# 2_MEMORY.net
KiCad netlist of a schematic drawn in Altium Designer
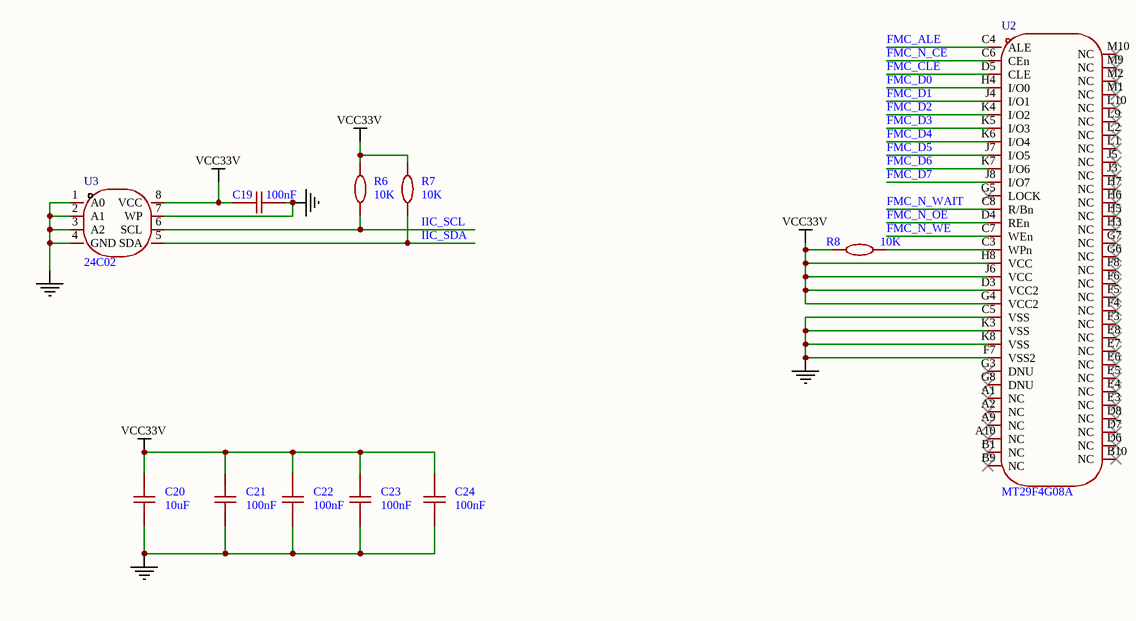
[diagram p0: 2_MEMORY.schdoc]

(export (version "E")
  (design (tool "Eeschema 10.0.6"))
  (components
    (comp (ref "C19")
      (value "100nF")
      (footprint "C0402")
      (libsource (lib "altium-import") (part "root_2_CAP_0402_"))
    )
    (comp (ref "C20")
      (value "10uF")
      (footprint "C0603")
      (libsource (lib "altium-import") (part "root_1_CAP_0603_"))
    )
    (comp (ref "C21")
      (value "100nF")
      (footprint "C0402")
      (libsource (lib "altium-import") (part "root_1_CAP_0402_"))
    )
    (comp (ref "C22")
      (value "100nF")
      (footprint "C0402")
      (libsource (lib "altium-import") (part "root_1_CAP_0402_"))
    )
    (comp (ref "C23")
      (value "100nF")
      (footprint "C0402")
      (libsource (lib "altium-import") (part "root_1_CAP_0402_"))
    )
    (comp (ref "C24")
      (value "100nF")
      (footprint "C0402")
      (libsource (lib "altium-import") (part "root_1_CAP_0402_"))
    )
    (comp (ref "R6")
      (value "10K")
      (footprint "R0402")
      (libsource (lib "altium-import") (part "root_1_Res_0402_"))
    )
    (comp (ref "R7")
      (value "10K")
      (footprint "R0402")
      (libsource (lib "altium-import") (part "root_1_Res_0402_"))
    )
    (comp (ref "R8")
      (value "10K")
      (footprint "R0402")
      (libsource (lib "altium-import") (part "root_0_Res_0402_"))
    )
    (comp (ref "U2")
      (value "MT29F4G08A")
      (footprint "VFBGA-63_L11.0-W9.0-P0.80-BL_MT29F2G08ABAEAH4-IT-E")
      (libsource (lib "altium-import") (part "root_0_MT29F4G08A_"))
    )
    (comp (ref "U3")
      (value "24C02")
      (footprint "SOP-8_L4.9-W3.9-P1.27-LS6.0-BL")
      (libsource (lib "altium-import") (part "root_0_24C02_"))
    )
  )
  (nets
    (net (code "1") (name "/FMC_ALE") (class "Default")
      (node (ref "U2") (pin "C4") (pinfunction "ALE_C4") (pintype "passive"))
    )
    (net (code "2") (name "/FMC_CLE") (class "Default")
      (node (ref "U2") (pin "D5") (pinfunction "CLE_D5") (pintype "passive"))
    )
    (net (code "3") (name "/FMC_D0") (class "Default")
      (node (ref "U2") (pin "H4") (pinfunction "I/O0_H4") (pintype "passive"))
    )
    (net (code "4") (name "/FMC_D1") (class "Default")
      (node (ref "U2") (pin "J4") (pinfunction "I/O1_J4") (pintype "passive"))
    )
    (net (code "5") (name "/FMC_D2") (class "Default")
      (node (ref "U2") (pin "K4") (pinfunction "I/O2_K4") (pintype "passive"))
    )
    (net (code "6") (name "/FMC_D3") (class "Default")
      (node (ref "U2") (pin "K5") (pinfunction "I/O3_K5") (pintype "passive"))
    )
    (net (code "7") (name "/FMC_D4") (class "Default")
      (node (ref "U2") (pin "K6") (pinfunction "I/O4_K6") (pintype "passive"))
    )
    (net (code "8") (name "/FMC_D5") (class "Default")
      (node (ref "U2") (pin "J7") (pinfunction "I/O5_J7") (pintype "passive"))
    )
    (net (code "9") (name "/FMC_D6") (class "Default")
      (node (ref "U2") (pin "K7") (pinfunction "I/O6_K7") (pintype "passive"))
    )
    (net (code "10") (name "/FMC_D7") (class "Default")
      (node (ref "U2") (pin "J8") (pinfunction "I/O7_J8") (pintype "passive"))
    )
    (net (code "11") (name "/FMC_N_CE") (class "Default")
      (node (ref "U2") (pin "C6") (pinfunction "CEn_C6") (pintype "passive"))
    )
    (net (code "12") (name "/FMC_N_OE") (class "Default")
      (node (ref "U2") (pin "D4") (pinfunction "REn_D4") (pintype "passive"))
    )
    (net (code "13") (name "/FMC_N_WAIT") (class "Default")
      (node (ref "U2") (pin "C8") (pinfunction "R/Bn_C8") (pintype "passive"))
    )
    (net (code "14") (name "/FMC_N_WE") (class "Default")
      (node (ref "U2") (pin "C7") (pinfunction "WEn_C7") (pintype "passive"))
    )
    (net (code "15") (name "/IIC_SCL") (class "Default")
      (node (ref "R6") (pin "1") (pinfunction "1_1") (pintype "passive"))
      (node (ref "U3") (pin "6") (pinfunction "SCL_6") (pintype "passive"))
    )
    (net (code "16") (name "/IIC_SDA") (class "Default")
      (node (ref "R7") (pin "1") (pinfunction "1_1") (pintype "passive"))
      (node (ref "U3") (pin "5") (pinfunction "SDA_5") (pintype "passive"))
    )
    (net (code "17") (name "DGND") (class "Default")
      (node (ref "C19") (pin "1") (pinfunction "1_1") (pintype "passive"))
      (node (ref "C20") (pin "1") (pinfunction "1_1") (pintype "passive"))
      (node (ref "C21") (pin "1") (pinfunction "1_1") (pintype "passive"))
      (node (ref "C22") (pin "1") (pinfunction "1_1") (pintype "passive"))
      (node (ref "C23") (pin "1") (pinfunction "1_1") (pintype "passive"))
      (node (ref "C24") (pin "1") (pinfunction "1_1") (pintype "passive"))
      (node (ref "U2") (pin "C5") (pinfunction "VSS_C5") (pintype "passive"))
      (node (ref "U2") (pin "F7") (pinfunction "VSS2_F7") (pintype "passive"))
      (node (ref "U2") (pin "K3") (pinfunction "VSS_K3") (pintype "passive"))
      (node (ref "U2") (pin "K8") (pinfunction "VSS_K8") (pintype "passive"))
      (node (ref "U3") (pin "1") (pinfunction "A0_1") (pintype "passive"))
      (node (ref "U3") (pin "2") (pinfunction "A1_2") (pintype "passive"))
      (node (ref "U3") (pin "3") (pinfunction "A2_3") (pintype "passive"))
      (node (ref "U3") (pin "4") (pinfunction "GND_4") (pintype "passive"))
      (node (ref "U3") (pin "7") (pinfunction "WP_7") (pintype "passive"))
    )
    (net (code "18") (name "Net-(U2-WPn)") (class "Default")
      (node (ref "R8") (pin "2") (pinfunction "2_2") (pintype "passive"))
      (node (ref "U2") (pin "C3") (pinfunction "WPn_C3") (pintype "passive"))
    )
    (net (code "19") (name "VCC33V") (class "Default")
      (node (ref "C19") (pin "2") (pinfunction "2_2") (pintype "passive"))
      (node (ref "C20") (pin "2") (pinfunction "2_2") (pintype "passive"))
      (node (ref "C21") (pin "2") (pinfunction "2_2") (pintype "passive"))
      (node (ref "C22") (pin "2") (pinfunction "2_2") (pintype "passive"))
      (node (ref "C23") (pin "2") (pinfunction "2_2") (pintype "passive"))
      (node (ref "C24") (pin "2") (pinfunction "2_2") (pintype "passive"))
      (node (ref "R6") (pin "2") (pinfunction "2_2") (pintype "passive"))
      (node (ref "R7") (pin "2") (pinfunction "2_2") (pintype "passive"))
      (node (ref "R8") (pin "1") (pinfunction "1_1") (pintype "passive"))
      (node (ref "U2") (pin "D3") (pinfunction "VCC2_D3") (pintype "passive"))
      (node (ref "U2") (pin "G4") (pinfunction "VCC2_G4") (pintype "passive"))
      (node (ref "U2") (pin "H8") (pinfunction "VCC_H8") (pintype "passive"))
      (node (ref "U2") (pin "J6") (pinfunction "VCC_J6") (pintype "passive"))
      (node (ref "U3") (pin "8") (pinfunction "VCC_8") (pintype "passive"))
    )
    (net (code "20") (name "unconnected-(U2-DNU-PadG3)") (class "Default")
      (node (ref "U2") (pin "G3") (pinfunction "DNU_G3") (pintype "passive+no_connect"))
    )
    (net (code "21") (name "unconnected-(U2-DNU-PadG8)") (class "Default")
      (node (ref "U2") (pin "G8") (pinfunction "DNU_G8") (pintype "passive+no_connect"))
    )
    (net (code "22") (name "unconnected-(U2-LOCK-PadG5)") (class "Default")
      (node (ref "U2") (pin "G5") (pinfunction "LOCK_G5") (pintype "passive+no_connect"))
    )
    (net (code "23") (name "unconnected-(U2-NC-PadA1)") (class "Default")
      (node (ref "U2") (pin "A1") (pinfunction "NC_A1") (pintype "passive+no_connect"))
    )
    (net (code "24") (name "unconnected-(U2-NC-PadA2)") (class "Default")
      (node (ref "U2") (pin "A2") (pinfunction "NC_A2") (pintype "passive+no_connect"))
    )
    (net (code "25") (name "unconnected-(U2-NC-PadA9)") (class "Default")
      (node (ref "U2") (pin "A9") (pinfunction "NC_A9") (pintype "passive+no_connect"))
    )
    (net (code "26") (name "unconnected-(U2-NC-PadA10)") (class "Default")
      (node (ref "U2") (pin "A10") (pinfunction "NC_A10") (pintype "passive+no_connect"))
    )
    (net (code "27") (name "unconnected-(U2-NC-PadB1)") (class "Default")
      (node (ref "U2") (pin "B1") (pinfunction "NC_B1") (pintype "passive+no_connect"))
    )
    (net (code "28") (name "unconnected-(U2-NC-PadB9)") (class "Default")
      (node (ref "U2") (pin "B9") (pinfunction "NC_B9") (pintype "passive+no_connect"))
    )
    (net (code "29") (name "unconnected-(U2-NC-PadB10)") (class "Default")
      (node (ref "U2") (pin "B10") (pinfunction "NC_B10") (pintype "passive+no_connect"))
    )
    (net (code "30") (name "unconnected-(U2-NC-PadD6)") (class "Default")
      (node (ref "U2") (pin "D6") (pinfunction "NC_D6") (pintype "passive+no_connect"))
    )
    (net (code "31") (name "unconnected-(U2-NC-PadD7)") (class "Default")
      (node (ref "U2") (pin "D7") (pinfunction "NC_D7") (pintype "passive+no_connect"))
    )
    (net (code "32") (name "unconnected-(U2-NC-PadD8)") (class "Default")
      (node (ref "U2") (pin "D8") (pinfunction "NC_D8") (pintype "passive+no_connect"))
    )
    (net (code "33") (name "unconnected-(U2-NC-PadE3)") (class "Default")
      (node (ref "U2") (pin "E3") (pinfunction "NC_E3") (pintype "passive+no_connect"))
    )
    (net (code "34") (name "unconnected-(U2-NC-PadE4)") (class "Default")
      (node (ref "U2") (pin "E4") (pinfunction "NC_E4") (pintype "passive+no_connect"))
    )
    (net (code "35") (name "unconnected-(U2-NC-PadE5)") (class "Default")
      (node (ref "U2") (pin "E5") (pinfunction "NC_E5") (pintype "passive+no_connect"))
    )
    (net (code "36") (name "unconnected-(U2-NC-PadE6)") (class "Default")
      (node (ref "U2") (pin "E6") (pinfunction "NC_E6") (pintype "passive+no_connect"))
    )
    (net (code "37") (name "unconnected-(U2-NC-PadE7)") (class "Default")
      (node (ref "U2") (pin "E7") (pinfunction "NC_E7") (pintype "passive+no_connect"))
    )
    (net (code "38") (name "unconnected-(U2-NC-PadE8)") (class "Default")
      (node (ref "U2") (pin "E8") (pinfunction "NC_E8") (pintype "passive+no_connect"))
    )
    (net (code "39") (name "unconnected-(U2-NC-PadF3)") (class "Default")
      (node (ref "U2") (pin "F3") (pinfunction "NC_F3") (pintype "passive+no_connect"))
    )
    (net (code "40") (name "unconnected-(U2-NC-PadF4)") (class "Default")
      (node (ref "U2") (pin "F4") (pinfunction "NC_F4") (pintype "passive+no_connect"))
    )
    (net (code "41") (name "unconnected-(U2-NC-PadF5)") (class "Default")
      (node (ref "U2") (pin "F5") (pinfunction "NC_F5") (pintype "passive+no_connect"))
    )
    (net (code "42") (name "unconnected-(U2-NC-PadF6)") (class "Default")
      (node (ref "U2") (pin "F6") (pinfunction "NC_F6") (pintype "passive+no_connect"))
    )
    (net (code "43") (name "unconnected-(U2-NC-PadF8)") (class "Default")
      (node (ref "U2") (pin "F8") (pinfunction "NC_F8") (pintype "passive+no_connect"))
    )
    (net (code "44") (name "unconnected-(U2-NC-PadG6)") (class "Default")
      (node (ref "U2") (pin "G6") (pinfunction "NC_G6") (pintype "passive+no_connect"))
    )
    (net (code "45") (name "unconnected-(U2-NC-PadG7)") (class "Default")
      (node (ref "U2") (pin "G7") (pinfunction "NC_G7") (pintype "passive+no_connect"))
    )
    (net (code "46") (name "unconnected-(U2-NC-PadH3)") (class "Default")
      (node (ref "U2") (pin "H3") (pinfunction "NC_H3") (pintype "passive+no_connect"))
    )
    (net (code "47") (name "unconnected-(U2-NC-PadH5)") (class "Default")
      (node (ref "U2") (pin "H5") (pinfunction "NC_H5") (pintype "passive+no_connect"))
    )
    (net (code "48") (name "unconnected-(U2-NC-PadH6)") (class "Default")
      (node (ref "U2") (pin "H6") (pinfunction "NC_H6") (pintype "passive+no_connect"))
    )
    (net (code "49") (name "unconnected-(U2-NC-PadH7)") (class "Default")
      (node (ref "U2") (pin "H7") (pinfunction "NC_H7") (pintype "passive+no_connect"))
    )
    (net (code "50") (name "unconnected-(U2-NC-PadJ3)") (class "Default")
      (node (ref "U2") (pin "J3") (pinfunction "NC_J3") (pintype "passive+no_connect"))
    )
    (net (code "51") (name "unconnected-(U2-NC-PadJ5)") (class "Default")
      (node (ref "U2") (pin "J5") (pinfunction "NC_J5") (pintype "passive+no_connect"))
    )
    (net (code "52") (name "unconnected-(U2-NC-PadL1)") (class "Default")
      (node (ref "U2") (pin "L1") (pinfunction "NC_L1") (pintype "passive+no_connect"))
    )
    (net (code "53") (name "unconnected-(U2-NC-PadL2)") (class "Default")
      (node (ref "U2") (pin "L2") (pinfunction "NC_L2") (pintype "passive+no_connect"))
    )
    (net (code "54") (name "unconnected-(U2-NC-PadL9)") (class "Default")
      (node (ref "U2") (pin "L9") (pinfunction "NC_L9") (pintype "passive+no_connect"))
    )
    (net (code "55") (name "unconnected-(U2-NC-PadL10)") (class "Default")
      (node (ref "U2") (pin "L10") (pinfunction "NC_L10") (pintype "passive+no_connect"))
    )
    (net (code "56") (name "unconnected-(U2-NC-PadM1)") (class "Default")
      (node (ref "U2") (pin "M1") (pinfunction "NC_M1") (pintype "passive+no_connect"))
    )
    (net (code "57") (name "unconnected-(U2-NC-PadM2)") (class "Default")
      (node (ref "U2") (pin "M2") (pinfunction "NC_M2") (pintype "passive+no_connect"))
    )
    (net (code "58") (name "unconnected-(U2-NC-PadM9)") (class "Default")
      (node (ref "U2") (pin "M9") (pinfunction "NC_M9") (pintype "passive+no_connect"))
    )
    (net (code "59") (name "unconnected-(U2-NC-PadM10)") (class "Default")
      (node (ref "U2") (pin "M10") (pinfunction "NC_M10") (pintype "passive+no_connect"))
    )
  )
)
